# BLDC_Controller.net
KiCad netlist of a schematic drawn in Altium Designer
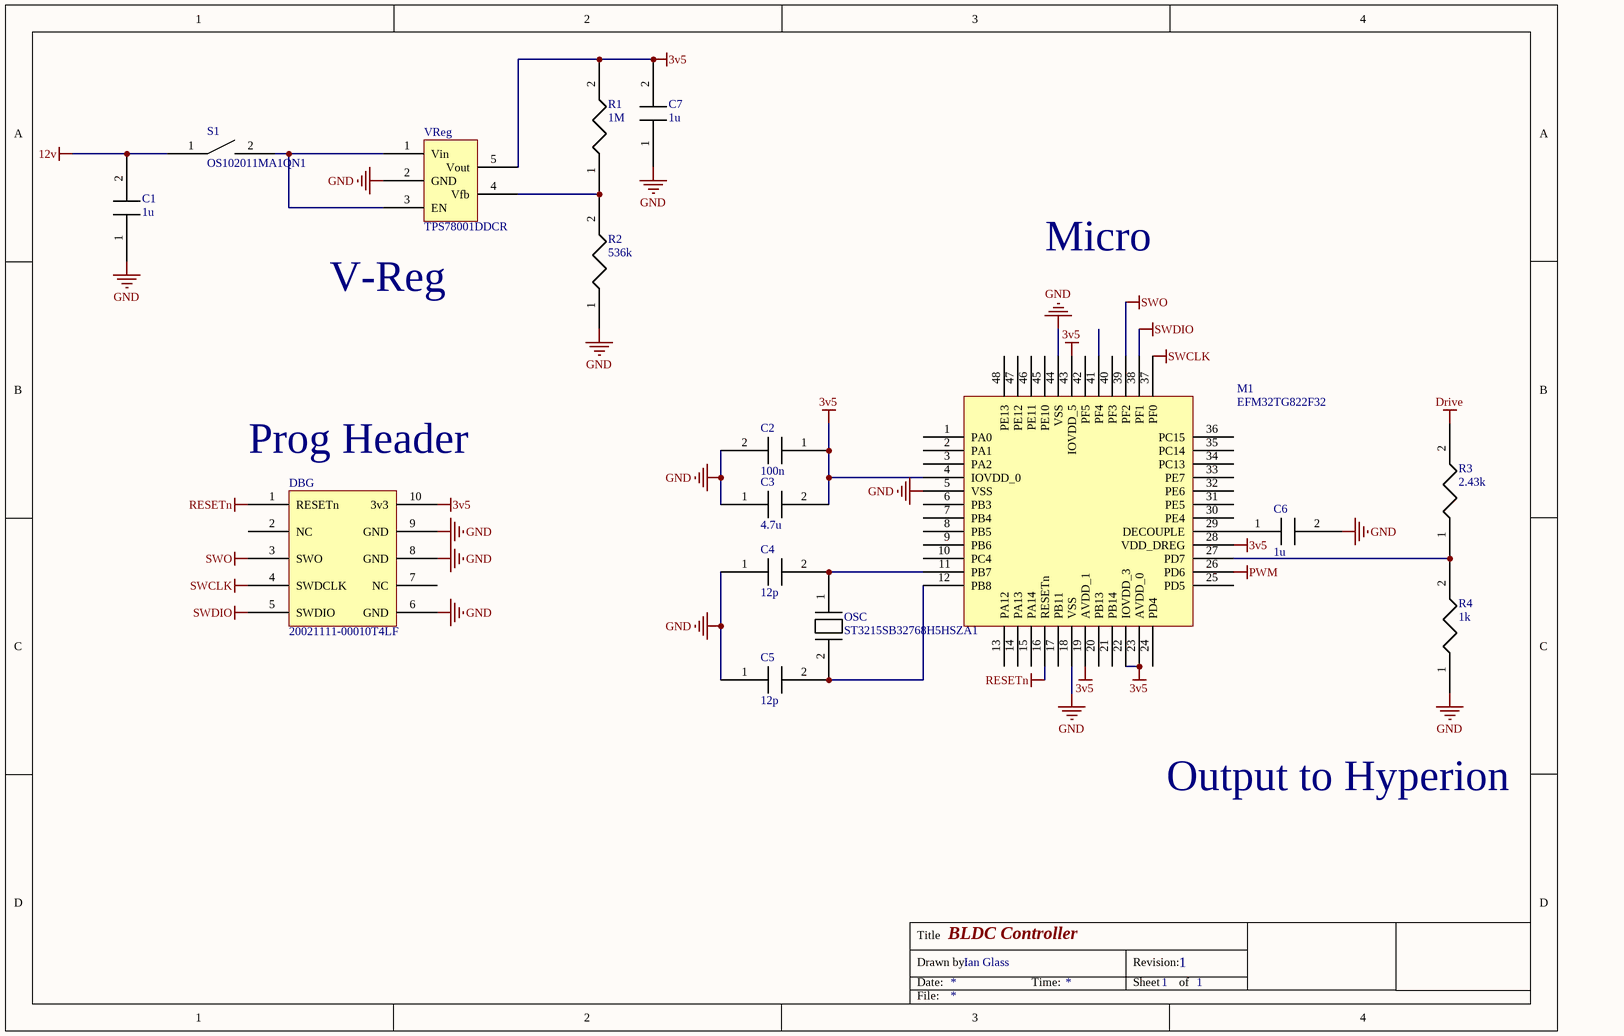
[diagram p0: BLDC_Controller.SchDoc]

(export (version "E")
  (design (tool "Eeschema 10.0.6"))
  (components
    (comp (ref "C1")
      (value "1u")
      (footprint "Capacitor 0402")
      (libsource (lib "WhereAbles") (part "Capacitor 0402"))
    )
    (comp (ref "C2")
      (value "100n")
      (footprint "Capacitor 0402")
      (libsource (lib "WhereAbles") (part "Capacitor 0402"))
    )
    (comp (ref "C3")
      (value "4.7u")
      (footprint "Capacitor 0603")
      (libsource (lib "BLDC Controller") (part "Capacitor 0603"))
    )
    (comp (ref "C4")
      (value "12p")
      (footprint "Capacitor 0402")
      (libsource (lib "NaviGo v4.0") (part "Capacitor 0402"))
    )
    (comp (ref "C5")
      (value "12p")
      (footprint "Capacitor 0402")
      (libsource (lib "NaviGo v4.0") (part "Capacitor 0402"))
    )
    (comp (ref "C6")
      (value "1u")
      (footprint "Capacitor 0402")
      (libsource (lib "WhereAbles") (part "Capacitor 0402"))
    )
    (comp (ref "C7")
      (value "1u")
      (footprint "Capacitor 0402")
      (libsource (lib "WhereAbles") (part "Capacitor 0402"))
    )
    (comp (ref "DBG")
      (value "20021111-00010T4LF")
      (footprint "20021111-00010T4LF")
      (libsource (lib "BLDC Controller") (part "20021111-00010T4LF"))
    )
    (comp (ref "M1")
      (value "EFM32TG822F32")
      (footprint "EFM32TG822F32")
      (libsource (lib "BLDC Controller") (part "EFM32TG822F32"))
    )
    (comp (ref "OSC")
      (value "ST3215SB32768H5HSZA1")
      (footprint "ST3215SB32768H5HSZA1")
      (libsource (lib "WhereAbles") (part "ST3215SB32768H5HSZA1"))
    )
    (comp (ref "R1")
      (value "1M")
      (footprint "Resistor 0402")
      (libsource (lib "BLDC Controller") (part "Resistor 0402"))
    )
    (comp (ref "R2")
      (value "536k")
      (footprint "Resistor 0603")
      (libsource (lib "WhereAbles") (part "Resistor 0603"))
    )
    (comp (ref "R3")
      (value "2.43k")
      (footprint "Resistor 0603")
      (libsource (lib "BLDC Controller") (part "Resistor 0603"))
    )
    (comp (ref "R4")
      (value "1k")
      (footprint "Resistor 0603")
      (libsource (lib "BLDC Controller") (part "Resistor 0603"))
    )
    (comp (ref "S1")
      (value "OS102011MA1QN1")
      (footprint "OS102011MA1QN1")
      (libsource (lib "BLDC Controller") (part "OS102011MA1QN1"))
    )
    (comp (ref "VReg")
      (value "TPS78001DDCR")
      (footprint "TPS78001DDCR")
      (libsource (lib "WhereAbles") (part "TPS78001DDCR"))
    )
  )
  (nets
    (net (code "1") (name "3v5") (class "Default")
      (node (ref "C2") (pin "1") (pinfunction "1_1") (pintype "passive"))
      (node (ref "C3") (pin "2") (pinfunction "2_2") (pintype "passive"))
      (node (ref "C7") (pin "2") (pinfunction "2_2") (pintype "passive"))
      (node (ref "DBG") (pin "10") (pinfunction "3v3_10") (pintype "passive"))
      (node (ref "M1") (pin "19") (pinfunction "AVDD_1_19") (pintype "passive"))
      (node (ref "M1") (pin "22") (pinfunction "IOVDD_3_22") (pintype "passive"))
      (node (ref "M1") (pin "23") (pinfunction "AVDD_0_23") (pintype "passive"))
      (node (ref "M1") (pin "28") (pinfunction "VDD_DREG_28") (pintype "passive"))
      (node (ref "M1") (pin "4") (pinfunction "IOVDD_0_4") (pintype "passive"))
      (node (ref "M1") (pin "43") (pinfunction "IOVDD_5_43") (pintype "passive"))
      (node (ref "R1") (pin "2") (pinfunction "2_2") (pintype "passive"))
      (node (ref "VReg") (pin "5") (pinfunction "Vout_5") (pintype "passive"))
    )
    (net (code "2") (name "12v") (class "Default")
      (node (ref "C1") (pin "2") (pinfunction "2_2") (pintype "passive"))
      (node (ref "S1") (pin "1") (pinfunction "1_1") (pintype "passive"))
    )
    (net (code "3") (name "Drive") (class "Default")
      (node (ref "R3") (pin "2") (pinfunction "2_2") (pintype "passive"))
    )
    (net (code "4") (name "GND") (class "Default")
      (node (ref "C1") (pin "1") (pinfunction "1_1") (pintype "passive"))
      (node (ref "C2") (pin "2") (pinfunction "2_2") (pintype "passive"))
      (node (ref "C3") (pin "1") (pinfunction "1_1") (pintype "passive"))
      (node (ref "C4") (pin "1") (pinfunction "1_1") (pintype "passive"))
      (node (ref "C5") (pin "1") (pinfunction "1_1") (pintype "passive"))
      (node (ref "C6") (pin "2") (pinfunction "2_2") (pintype "passive"))
      (node (ref "C7") (pin "1") (pinfunction "1_1") (pintype "passive"))
      (node (ref "DBG") (pin "6") (pinfunction "GND_6") (pintype "passive"))
      (node (ref "DBG") (pin "8") (pinfunction "GND_8") (pintype "passive"))
      (node (ref "DBG") (pin "9") (pinfunction "GND_9") (pintype "passive"))
      (node (ref "M1") (pin "18") (pinfunction "VSS_18") (pintype "passive"))
      (node (ref "M1") (pin "44") (pinfunction "VSS_44") (pintype "passive"))
      (node (ref "M1") (pin "5") (pinfunction "VSS_5") (pintype "passive"))
      (node (ref "R2") (pin "1") (pinfunction "1_1") (pintype "passive"))
      (node (ref "R4") (pin "1") (pinfunction "1_1") (pintype "passive"))
      (node (ref "VReg") (pin "2") (pinfunction "GND_2") (pintype "passive"))
    )
    (net (code "5") (name "Net-(M1-DECOUPLE)") (class "Default")
      (node (ref "C6") (pin "1") (pinfunction "1_1") (pintype "passive"))
      (node (ref "M1") (pin "29") (pinfunction "DECOUPLE_29") (pintype "passive"))
    )
    (net (code "6") (name "Net-(M1-PB7)") (class "Default")
      (node (ref "C4") (pin "2") (pinfunction "2_2") (pintype "passive"))
      (node (ref "M1") (pin "11") (pinfunction "PB7_11") (pintype "passive"))
      (node (ref "OSC") (pin "1") (pinfunction "1_1") (pintype "passive"))
    )
    (net (code "7") (name "Net-(M1-PB8)") (class "Default")
      (node (ref "C5") (pin "2") (pinfunction "2_2") (pintype "passive"))
      (node (ref "M1") (pin "12") (pinfunction "PB8_12") (pintype "passive"))
      (node (ref "OSC") (pin "2") (pinfunction "2_2") (pintype "passive"))
    )
    (net (code "8") (name "Net-(M1-PD7)") (class "Default")
      (node (ref "M1") (pin "27") (pinfunction "PD7_27") (pintype "passive"))
      (node (ref "R3") (pin "1") (pinfunction "1_1") (pintype "passive"))
      (node (ref "R4") (pin "2") (pinfunction "2_2") (pintype "passive"))
    )
    (net (code "9") (name "Net-(VReg-EN)") (class "Default")
      (node (ref "S1") (pin "2") (pinfunction "2_2") (pintype "passive"))
      (node (ref "VReg") (pin "1") (pinfunction "Vin_1") (pintype "passive"))
      (node (ref "VReg") (pin "3") (pinfunction "EN_3") (pintype "passive"))
    )
    (net (code "10") (name "Net-(VReg-Vfb)") (class "Default")
      (node (ref "R1") (pin "1") (pinfunction "1_1") (pintype "passive"))
      (node (ref "R2") (pin "2") (pinfunction "2_2") (pintype "passive"))
      (node (ref "VReg") (pin "4") (pinfunction "Vfb_4") (pintype "passive"))
    )
    (net (code "11") (name "PWM") (class "Default")
      (node (ref "M1") (pin "26") (pinfunction "PD6_26") (pintype "passive"))
    )
    (net (code "12") (name "RESETn") (class "Default")
      (node (ref "DBG") (pin "1") (pinfunction "RESETn_1") (pintype "passive"))
      (node (ref "M1") (pin "16") (pinfunction "RESETn_16") (pintype "passive"))
    )
    (net (code "13") (name "SWCLK") (class "Default")
      (node (ref "DBG") (pin "4") (pinfunction "SWDCLK_4") (pintype "passive"))
      (node (ref "M1") (pin "37") (pinfunction "PF0_37") (pintype "passive"))
    )
    (net (code "14") (name "SWDIO") (class "Default")
      (node (ref "DBG") (pin "5") (pinfunction "SWDIO_5") (pintype "passive"))
      (node (ref "M1") (pin "38") (pinfunction "PF1_38") (pintype "passive"))
    )
    (net (code "15") (name "SWO") (class "Default")
      (node (ref "DBG") (pin "3") (pinfunction "SWO_3") (pintype "passive"))
      (node (ref "M1") (pin "39") (pinfunction "PF2_39") (pintype "passive"))
    )
    (net (code "16") (name "unconnected-(DBG-NC-Pad2)") (class "Default")
      (node (ref "DBG") (pin "2") (pinfunction "NC_2") (pintype "passive"))
    )
    (net (code "17") (name "unconnected-(DBG-NC-Pad7)") (class "Default")
      (node (ref "DBG") (pin "7") (pinfunction "NC_7") (pintype "passive"))
    )
    (net (code "18") (name "unconnected-(M1-PA0-Pad1)") (class "Default")
      (node (ref "M1") (pin "1") (pinfunction "PA0_1") (pintype "passive"))
    )
    (net (code "19") (name "unconnected-(M1-PA1-Pad2)") (class "Default")
      (node (ref "M1") (pin "2") (pinfunction "PA1_2") (pintype "passive"))
    )
    (net (code "20") (name "unconnected-(M1-PA2-Pad3)") (class "Default")
      (node (ref "M1") (pin "3") (pinfunction "PA2_3") (pintype "passive"))
    )
    (net (code "21") (name "unconnected-(M1-PA12-Pad13)") (class "Default")
      (node (ref "M1") (pin "13") (pinfunction "PA12_13") (pintype "passive"))
    )
    (net (code "22") (name "unconnected-(M1-PA13-Pad14)") (class "Default")
      (node (ref "M1") (pin "14") (pinfunction "PA13_14") (pintype "passive"))
    )
    (net (code "23") (name "unconnected-(M1-PA14-Pad15)") (class "Default")
      (node (ref "M1") (pin "15") (pinfunction "PA14_15") (pintype "passive"))
    )
    (net (code "24") (name "unconnected-(M1-PB3-Pad6)") (class "Default")
      (node (ref "M1") (pin "6") (pinfunction "PB3_6") (pintype "passive"))
    )
    (net (code "25") (name "unconnected-(M1-PB4-Pad7)") (class "Default")
      (node (ref "M1") (pin "7") (pinfunction "PB4_7") (pintype "passive"))
    )
    (net (code "26") (name "unconnected-(M1-PB5-Pad8)") (class "Default")
      (node (ref "M1") (pin "8") (pinfunction "PB5_8") (pintype "passive"))
    )
    (net (code "27") (name "unconnected-(M1-PB6-Pad9)") (class "Default")
      (node (ref "M1") (pin "9") (pinfunction "PB6_9") (pintype "passive"))
    )
    (net (code "28") (name "unconnected-(M1-PB11-Pad17)") (class "Default")
      (node (ref "M1") (pin "17") (pinfunction "PB11_17") (pintype "passive"))
    )
    (net (code "29") (name "unconnected-(M1-PB13-Pad20)") (class "Default")
      (node (ref "M1") (pin "20") (pinfunction "PB13_20") (pintype "passive"))
    )
    (net (code "30") (name "unconnected-(M1-PB14-Pad21)") (class "Default")
      (node (ref "M1") (pin "21") (pinfunction "PB14_21") (pintype "passive"))
    )
    (net (code "31") (name "unconnected-(M1-PC4-Pad10)") (class "Default")
      (node (ref "M1") (pin "10") (pinfunction "PC4_10") (pintype "passive"))
    )
    (net (code "32") (name "unconnected-(M1-PC13-Pad34)") (class "Default")
      (node (ref "M1") (pin "34") (pinfunction "PC13_34") (pintype "passive"))
    )
    (net (code "33") (name "unconnected-(M1-PC14-Pad35)") (class "Default")
      (node (ref "M1") (pin "35") (pinfunction "PC14_35") (pintype "passive"))
    )
    (net (code "34") (name "unconnected-(M1-PC15-Pad36)") (class "Default")
      (node (ref "M1") (pin "36") (pinfunction "PC15_36") (pintype "passive"))
    )
    (net (code "35") (name "unconnected-(M1-PD4-Pad24)") (class "Default")
      (node (ref "M1") (pin "24") (pinfunction "PD4_24") (pintype "passive"))
    )
    (net (code "36") (name "unconnected-(M1-PD5-Pad25)") (class "Default")
      (node (ref "M1") (pin "25") (pinfunction "PD5_25") (pintype "passive"))
    )
    (net (code "37") (name "unconnected-(M1-PE4-Pad30)") (class "Default")
      (node (ref "M1") (pin "30") (pinfunction "PE4_30") (pintype "passive"))
    )
    (net (code "38") (name "unconnected-(M1-PE5-Pad31)") (class "Default")
      (node (ref "M1") (pin "31") (pinfunction "PE5_31") (pintype "passive"))
    )
    (net (code "39") (name "unconnected-(M1-PE6-Pad32)") (class "Default")
      (node (ref "M1") (pin "32") (pinfunction "PE6_32") (pintype "passive"))
    )
    (net (code "40") (name "unconnected-(M1-PE7-Pad33)") (class "Default")
      (node (ref "M1") (pin "33") (pinfunction "PE7_33") (pintype "passive"))
    )
    (net (code "41") (name "unconnected-(M1-PE10-Pad45)") (class "Default")
      (node (ref "M1") (pin "45") (pinfunction "PE10_45") (pintype "passive"))
    )
    (net (code "42") (name "unconnected-(M1-PE11-Pad46)") (class "Default")
      (node (ref "M1") (pin "46") (pinfunction "PE11_46") (pintype "passive"))
    )
    (net (code "43") (name "unconnected-(M1-PE12-Pad47)") (class "Default")
      (node (ref "M1") (pin "47") (pinfunction "PE12_47") (pintype "passive"))
    )
    (net (code "44") (name "unconnected-(M1-PE13-Pad48)") (class "Default")
      (node (ref "M1") (pin "48") (pinfunction "PE13_48") (pintype "passive"))
    )
    (net (code "45") (name "unconnected-(M1-PF3-Pad40)") (class "Default")
      (node (ref "M1") (pin "40") (pinfunction "PF3_40") (pintype "passive"))
    )
    (net (code "46") (name "unconnected-(M1-PF4-Pad41)") (class "Default")
      (node (ref "M1") (pin "41") (pinfunction "PF4_41") (pintype "passive"))
    )
    (net (code "47") (name "unconnected-(M1-PF5-Pad42)") (class "Default")
      (node (ref "M1") (pin "42") (pinfunction "PF5_42") (pintype "passive"))
    )
  )
)
